# Interfaces.net
KiCad netlist of a schematic drawn in Altium Designer
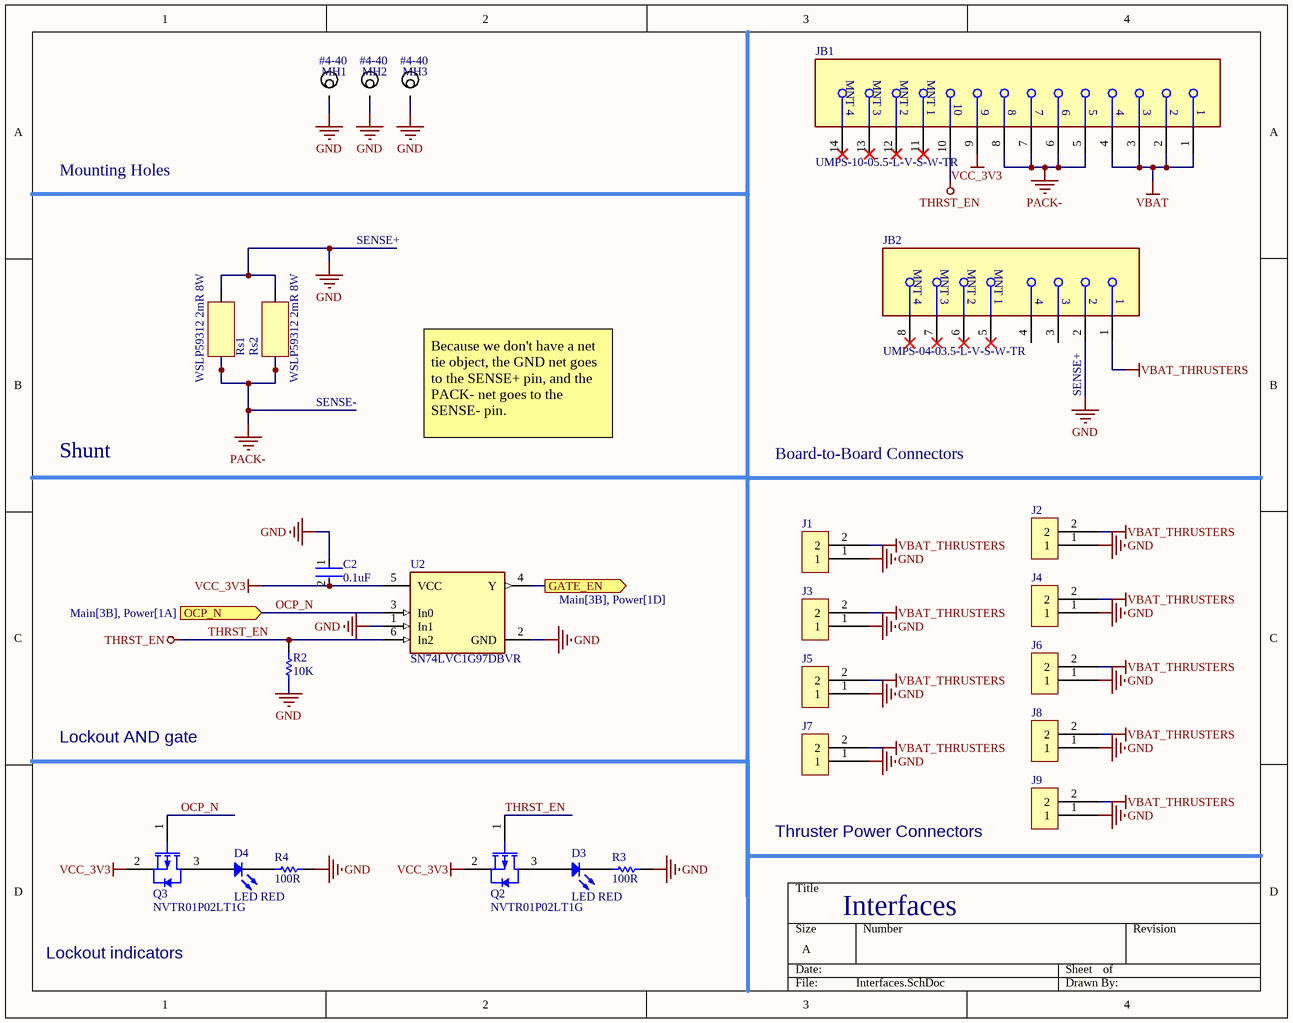
[diagram p0: Interfaces.SchDoc]

(export (version "E")
  (design (tool "Eeschema 10.0.6"))
  (components
    (comp (ref "C2")
      (value "0.1uF")
      (footprint "FP-C0603C-CF-MFG")
      (description "CAP CER 0.1UF 10V X7R 0603")
      (fields (field (name "TOLERANCE") "0.1") (field (name "MANUFACTURER PART NUMBER") "C0603C104K8RACTU"))
      (libsource (lib "Altium Content Vault") (part "b4654b650e69147ec39a6b967a45e02"))
    )
    (comp (ref "D3")
      (value "LED RED")
      (footprint "C0805")
      (description "led\r\n LTST-C171KRKT")
      (fields
        (field (name "MANUFACTURER") "Lite-On Inc.")
        (field (name "MANUFACTURER PART NUMBER") "LTST-C171KRKT")
      )
      (libsource (lib "CMR_Miscellaneous_Devices") (part "LED0"))
    )
    (comp (ref "D4")
      (value "LED RED")
      (footprint "C0805")
      (description "led\r\n LTST-C171KRKT")
      (fields
        (field (name "MANUFACTURER") "Lite-On Inc.")
        (field (name "MANUFACTURER PART NUMBER") "LTST-C171KRKT")
      )
      (libsource (lib "CMR_Miscellaneous_Devices") (part "LED0"))
    )
    (comp (ref "J1")
      (value "~")
      (footprint "2-pin Megafit RA")
      (libsource (lib "TAUV-Lib") (part "2-pin megafit"))
    )
    (comp (ref "J2")
      (value "~")
      (footprint "2-pin Megafit RA")
      (libsource (lib "TAUV-Lib") (part "2-pin megafit"))
    )
    (comp (ref "J3")
      (value "~")
      (footprint "2-pin Megafit RA")
      (libsource (lib "TAUV-Lib") (part "2-pin megafit"))
    )
    (comp (ref "J4")
      (value "~")
      (footprint "2-pin Megafit RA")
      (libsource (lib "TAUV-Lib") (part "2-pin megafit"))
    )
    (comp (ref "J5")
      (value "~")
      (footprint "2-pin Megafit RA")
      (libsource (lib "TAUV-Lib") (part "2-pin megafit"))
    )
    (comp (ref "J6")
      (value "~")
      (footprint "2-pin Megafit RA")
      (libsource (lib "TAUV-Lib") (part "2-pin megafit"))
    )
    (comp (ref "J7")
      (value "~")
      (footprint "2-pin Megafit RA")
      (libsource (lib "TAUV-Lib") (part "2-pin megafit"))
    )
    (comp (ref "J8")
      (value "~")
      (footprint "2-pin Megafit RA")
      (libsource (lib "TAUV-Lib") (part "2-pin megafit"))
    )
    (comp (ref "J9")
      (value "~")
      (footprint "2-pin Megafit RA")
      (libsource (lib "Tauv-Lib") (part "2-pin megafit"))
    )
    (comp (ref "JB1")
      (value "UMPS-10-05.5-L-V-S-W-TR")
      (footprint "FP-UMPS-10-05_5-L-V-S-W-T-MFG")
      (description "CONN MPOWER 2MM FMALE 10POS GOLD")
      (libsource (lib "Altium Content Vault") (part "50ca1e906762132617f05a77d1e0c4c"))
    )
    (comp (ref "JB2")
      (value "UMPS-04-03.5-L-V-S-W-TR")
      (footprint "FP-UMPS-04-03_5-L-V-S-W-T-MFG")
      (description "CONN MPOWER 2MM FMALE 4POS GOLD")
      (libsource (lib "Altium Content Vault") (part "04dfb715127717a7ff8d0007f751750"))
    )
    (comp (ref "MH1")
      (value "#4-40")
      (footprint "Mounting Hole #4-40")
      (description "Mounting Hole for ANSI #4-40 w/ Flat Washer, Loose Fit")
      (libsource (lib "TAUV-Lib") (part "Mounting Hole #4-40, Loose Fit"))
    )
    (comp (ref "MH2")
      (value "#4-40")
      (footprint "Mounting Hole #4-40")
      (description "Mounting Hole for ANSI #4-40 w/ Flat Washer, Loose Fit")
      (libsource (lib "TAUV-Lib") (part "Mounting Hole #4-40, Loose Fit"))
    )
    (comp (ref "MH3")
      (value "#4-40")
      (footprint "Mounting Hole #4-40")
      (description "Mounting Hole for ANSI #4-40 w/ Flat Washer, Loose Fit")
      (libsource (lib "TAUV-Lib") (part "Mounting Hole #4-40, Loose Fit"))
    )
    (comp (ref "Q2")
      (value "NVTR01P02LT1G")
      (footprint "ONSC-SOT-23-3-318-08_V")
      (description "Power MOSFET, -20 V, -1.3 A, P-Channel, 3-Pin SOT-23, Pb-Free, Tape and Reel")
      (fields (field (name "MANUFACTURER") "On Semiconductor"))
      (libsource (lib "Altium Content Vault") (part "ONSC-PMOS-G1S2D3-3_D"))
    )
    (comp (ref "Q3")
      (value "NVTR01P02LT1G")
      (footprint "ONSC-SOT-23-3-318-08_V")
      (description "Power MOSFET, -20 V, -1.3 A, P-Channel, 3-Pin SOT-23, Pb-Free, Tape and Reel")
      (fields (field (name "MANUFACTURER") "On Semiconductor"))
      (libsource (lib "Altium Content Vault") (part "ONSC-PMOS-G1S2D3-3_D"))
    )
    (comp (ref "R2")
      (value "10K")
      (footprint "RESC0603(1608)_N")
      (description "10K 0.1W 5% 0603 (1608 Metric)  SMD")
      (fields (field (name "TOLERANCE") "5 %") (field (name "POWER") "0.1 W"))
      (libsource (lib "Altium Content Vault") (part "RES"))
    )
    (comp (ref "R3")
      (value "100R")
      (footprint "RESC1609X50X30NL10T20")
      (description "100R 0.1W 5%")
      (fields (field (name "PART NUMBER") "CRCW0603100RJNTA") (field (name "MANUFACTURER") "Vishay Dale"))
      (libsource (lib "Altium Content Vault") (part "RES"))
    )
    (comp (ref "R4")
      (value "100R")
      (footprint "RESC1609X50X30NL10T20")
      (description "100R 0.1W 5%")
      (fields (field (name "PART NUMBER") "CRCW0603100RJNTA") (field (name "MANUFACTURER") "Vishay Dale"))
      (libsource (lib "Altium Content Vault") (part "RES"))
    )
    (comp (ref "Rs1")
      (value "WSLP59312 2mR 8W")
      (footprint "WSLP59312L000FEA")
      (libsource (lib "Tauv-Lib") (part "WSLP59312L000FEA"))
    )
    (comp (ref "Rs2")
      (value "WSLP59312 2mR 8W")
      (footprint "WSLP59312L000FEA")
      (libsource (lib "Tauv-Lib") (part "WSLP59312L000FEA"))
    )
    (comp (ref "U2")
      (value "SN74LVC1G97DBVR")
      (footprint "FP-DBV0006A-MFG")
      (description "IC CONFIG MULT-FUNC GATE SOT23-6")
      (fields
        (field (name "OCTOPART") "https://octopart.com/sn74lvc1g97dbvr-texas+instruments-464842")
        (field (name "MANUFACTURER") "Texas Instruments")
      )
      (libsource (lib "Altium Content Vault") (part "a1876f62f2ab2790f28bb26e63f2887"))
    )
  )
  (nets
    (net (code "1") (name "/GATE_EN") (class "Default")
      (node (ref "U2") (pin "4") (pinfunction "Y_4") (pintype "output"))
    )
    (net (code "2") (name "/OCP_N") (class "Default")
      (node (ref "Q3") (pin "1") (pinfunction "G_1") (pintype "passive"))
      (node (ref "U2") (pin "3") (pinfunction "In0_3") (pintype "input"))
    )
    (net (code "3") (name "GND") (class "Default")
      (node (ref "C2") (pin "1") (pinfunction "1_1") (pintype "passive"))
      (node (ref "J1") (pin "1") (pinfunction "1_1") (pintype "passive"))
      (node (ref "J2") (pin "1") (pinfunction "1_1") (pintype "passive"))
      (node (ref "J3") (pin "1") (pinfunction "1_1") (pintype "passive"))
      (node (ref "J4") (pin "1") (pinfunction "1_1") (pintype "passive"))
      (node (ref "J5") (pin "1") (pinfunction "1_1") (pintype "passive"))
      (node (ref "J6") (pin "1") (pinfunction "1_1") (pintype "passive"))
      (node (ref "J7") (pin "1") (pinfunction "1_1") (pintype "passive"))
      (node (ref "J8") (pin "1") (pinfunction "1_1") (pintype "passive"))
      (node (ref "J9") (pin "1") (pinfunction "1_1") (pintype "passive"))
      (node (ref "JB2") (pin "2") (pinfunction "2_2") (pintype "passive"))
      (node (ref "MH1") (pin "0") (pinfunction "0_0") (pintype "passive"))
      (node (ref "MH2") (pin "0") (pinfunction "0_0") (pintype "passive"))
      (node (ref "MH3") (pin "0") (pinfunction "0_0") (pintype "passive"))
      (node (ref "R2") (pin "2") (pinfunction "2_2") (pintype "passive"))
      (node (ref "R3") (pin "2") (pinfunction "2_2") (pintype "passive"))
      (node (ref "R4") (pin "2") (pinfunction "2_2") (pintype "passive"))
      (node (ref "Rs1") (pin "2") (pinfunction "2_2") (pintype "passive"))
      (node (ref "Rs2") (pin "2") (pinfunction "2_2") (pintype "passive"))
      (node (ref "U2") (pin "1") (pinfunction "In1_1") (pintype "input"))
      (node (ref "U2") (pin "2") (pinfunction "GND_2") (pintype "power_in"))
    )
    (net (code "4") (name "Net-(D3-A)") (class "Default")
      (node (ref "D3") (pin "2") (pinfunction "A_2") (pintype "passive"))
      (node (ref "Q2") (pin "3") (pinfunction "D_3") (pintype "passive"))
    )
    (net (code "5") (name "Net-(D3-K)") (class "Default")
      (node (ref "D3") (pin "1") (pinfunction "K_1") (pintype "passive"))
      (node (ref "R3") (pin "1") (pinfunction "1_1") (pintype "passive"))
    )
    (net (code "6") (name "Net-(D4-A)") (class "Default")
      (node (ref "D4") (pin "2") (pinfunction "A_2") (pintype "passive"))
      (node (ref "Q3") (pin "3") (pinfunction "D_3") (pintype "passive"))
    )
    (net (code "7") (name "Net-(D4-K)") (class "Default")
      (node (ref "D4") (pin "1") (pinfunction "K_1") (pintype "passive"))
      (node (ref "R4") (pin "1") (pinfunction "1_1") (pintype "passive"))
    )
    (net (code "8") (name "PACK-") (class "Default")
      (node (ref "JB1") (pin "5") (pinfunction "5_5") (pintype "passive"))
      (node (ref "JB1") (pin "6") (pinfunction "6_6") (pintype "passive"))
      (node (ref "JB1") (pin "7") (pinfunction "7_7") (pintype "passive"))
      (node (ref "JB1") (pin "8") (pinfunction "8_8") (pintype "passive"))
      (node (ref "Rs1") (pin "1") (pinfunction "1_1") (pintype "passive"))
      (node (ref "Rs2") (pin "1") (pinfunction "1_1") (pintype "passive"))
    )
    (net (code "9") (name "THRST_EN") (class "Default")
      (node (ref "JB1") (pin "10") (pinfunction "10_10") (pintype "passive"))
      (node (ref "Q2") (pin "1") (pinfunction "G_1") (pintype "passive"))
      (node (ref "R2") (pin "1") (pinfunction "1_1") (pintype "passive"))
      (node (ref "U2") (pin "6") (pinfunction "In2_6") (pintype "input"))
    )
    (net (code "10") (name "VBAT") (class "Default")
      (node (ref "JB1") (pin "1") (pinfunction "1_1") (pintype "passive"))
      (node (ref "JB1") (pin "2") (pinfunction "2_2") (pintype "passive"))
      (node (ref "JB1") (pin "3") (pinfunction "3_3") (pintype "passive"))
      (node (ref "JB1") (pin "4") (pinfunction "4_4") (pintype "passive"))
    )
    (net (code "11") (name "VBAT_THRUSTERS") (class "Default")
      (node (ref "J1") (pin "2") (pinfunction "2_2") (pintype "passive"))
      (node (ref "J2") (pin "2") (pinfunction "2_2") (pintype "passive"))
      (node (ref "J3") (pin "2") (pinfunction "2_2") (pintype "passive"))
      (node (ref "J4") (pin "2") (pinfunction "2_2") (pintype "passive"))
      (node (ref "J5") (pin "2") (pinfunction "2_2") (pintype "passive"))
      (node (ref "J6") (pin "2") (pinfunction "2_2") (pintype "passive"))
      (node (ref "J7") (pin "2") (pinfunction "2_2") (pintype "passive"))
      (node (ref "J8") (pin "2") (pinfunction "2_2") (pintype "passive"))
      (node (ref "J9") (pin "2") (pinfunction "2_2") (pintype "passive"))
      (node (ref "JB2") (pin "1") (pinfunction "1_1") (pintype "passive"))
    )
    (net (code "12") (name "VCC_3V3") (class "Default")
      (node (ref "C2") (pin "2") (pinfunction "2_2") (pintype "passive"))
      (node (ref "JB1") (pin "9") (pinfunction "9_9") (pintype "passive"))
      (node (ref "Q2") (pin "2") (pinfunction "S_2") (pintype "passive"))
      (node (ref "Q3") (pin "2") (pinfunction "S_2") (pintype "passive"))
      (node (ref "U2") (pin "5") (pinfunction "VCC_5") (pintype "power_in"))
    )
    (net (code "13") (name "unconnected-(JB1-MNT_1-Pad11)") (class "Default")
      (node (ref "JB1") (pin "11") (pinfunction "MNT_1_11") (pintype "passive+no_connect"))
    )
    (net (code "14") (name "unconnected-(JB1-MNT_2-Pad12)") (class "Default")
      (node (ref "JB1") (pin "12") (pinfunction "MNT_2_12") (pintype "passive+no_connect"))
    )
    (net (code "15") (name "unconnected-(JB1-MNT_3-Pad13)") (class "Default")
      (node (ref "JB1") (pin "13") (pinfunction "MNT_3_13") (pintype "passive+no_connect"))
    )
    (net (code "16") (name "unconnected-(JB1-MNT_4-Pad14)") (class "Default")
      (node (ref "JB1") (pin "14") (pinfunction "MNT_4_14") (pintype "passive+no_connect"))
    )
    (net (code "17") (name "unconnected-(JB2-MNT_1-Pad5)") (class "Default")
      (node (ref "JB2") (pin "5") (pinfunction "MNT_1_5") (pintype "passive+no_connect"))
    )
    (net (code "18") (name "unconnected-(JB2-MNT_2-Pad6)") (class "Default")
      (node (ref "JB2") (pin "6") (pinfunction "MNT_2_6") (pintype "passive+no_connect"))
    )
    (net (code "19") (name "unconnected-(JB2-MNT_3-Pad7)") (class "Default")
      (node (ref "JB2") (pin "7") (pinfunction "MNT_3_7") (pintype "passive+no_connect"))
    )
    (net (code "20") (name "unconnected-(JB2-MNT_4-Pad8)") (class "Default")
      (node (ref "JB2") (pin "8") (pinfunction "MNT_4_8") (pintype "passive+no_connect"))
    )
    (net (code "21") (name "unconnected-(JB2-Pad3)") (class "Default")
      (node (ref "JB2") (pin "3") (pinfunction "3_3") (pintype "passive"))
    )
    (net (code "22") (name "unconnected-(JB2-Pad4)") (class "Default")
      (node (ref "JB2") (pin "4") (pinfunction "4_4") (pintype "passive"))
    )
  )
)
